# ScenOchSinneSensor.net
KiCad netlist of a schematic drawn in EAGLE
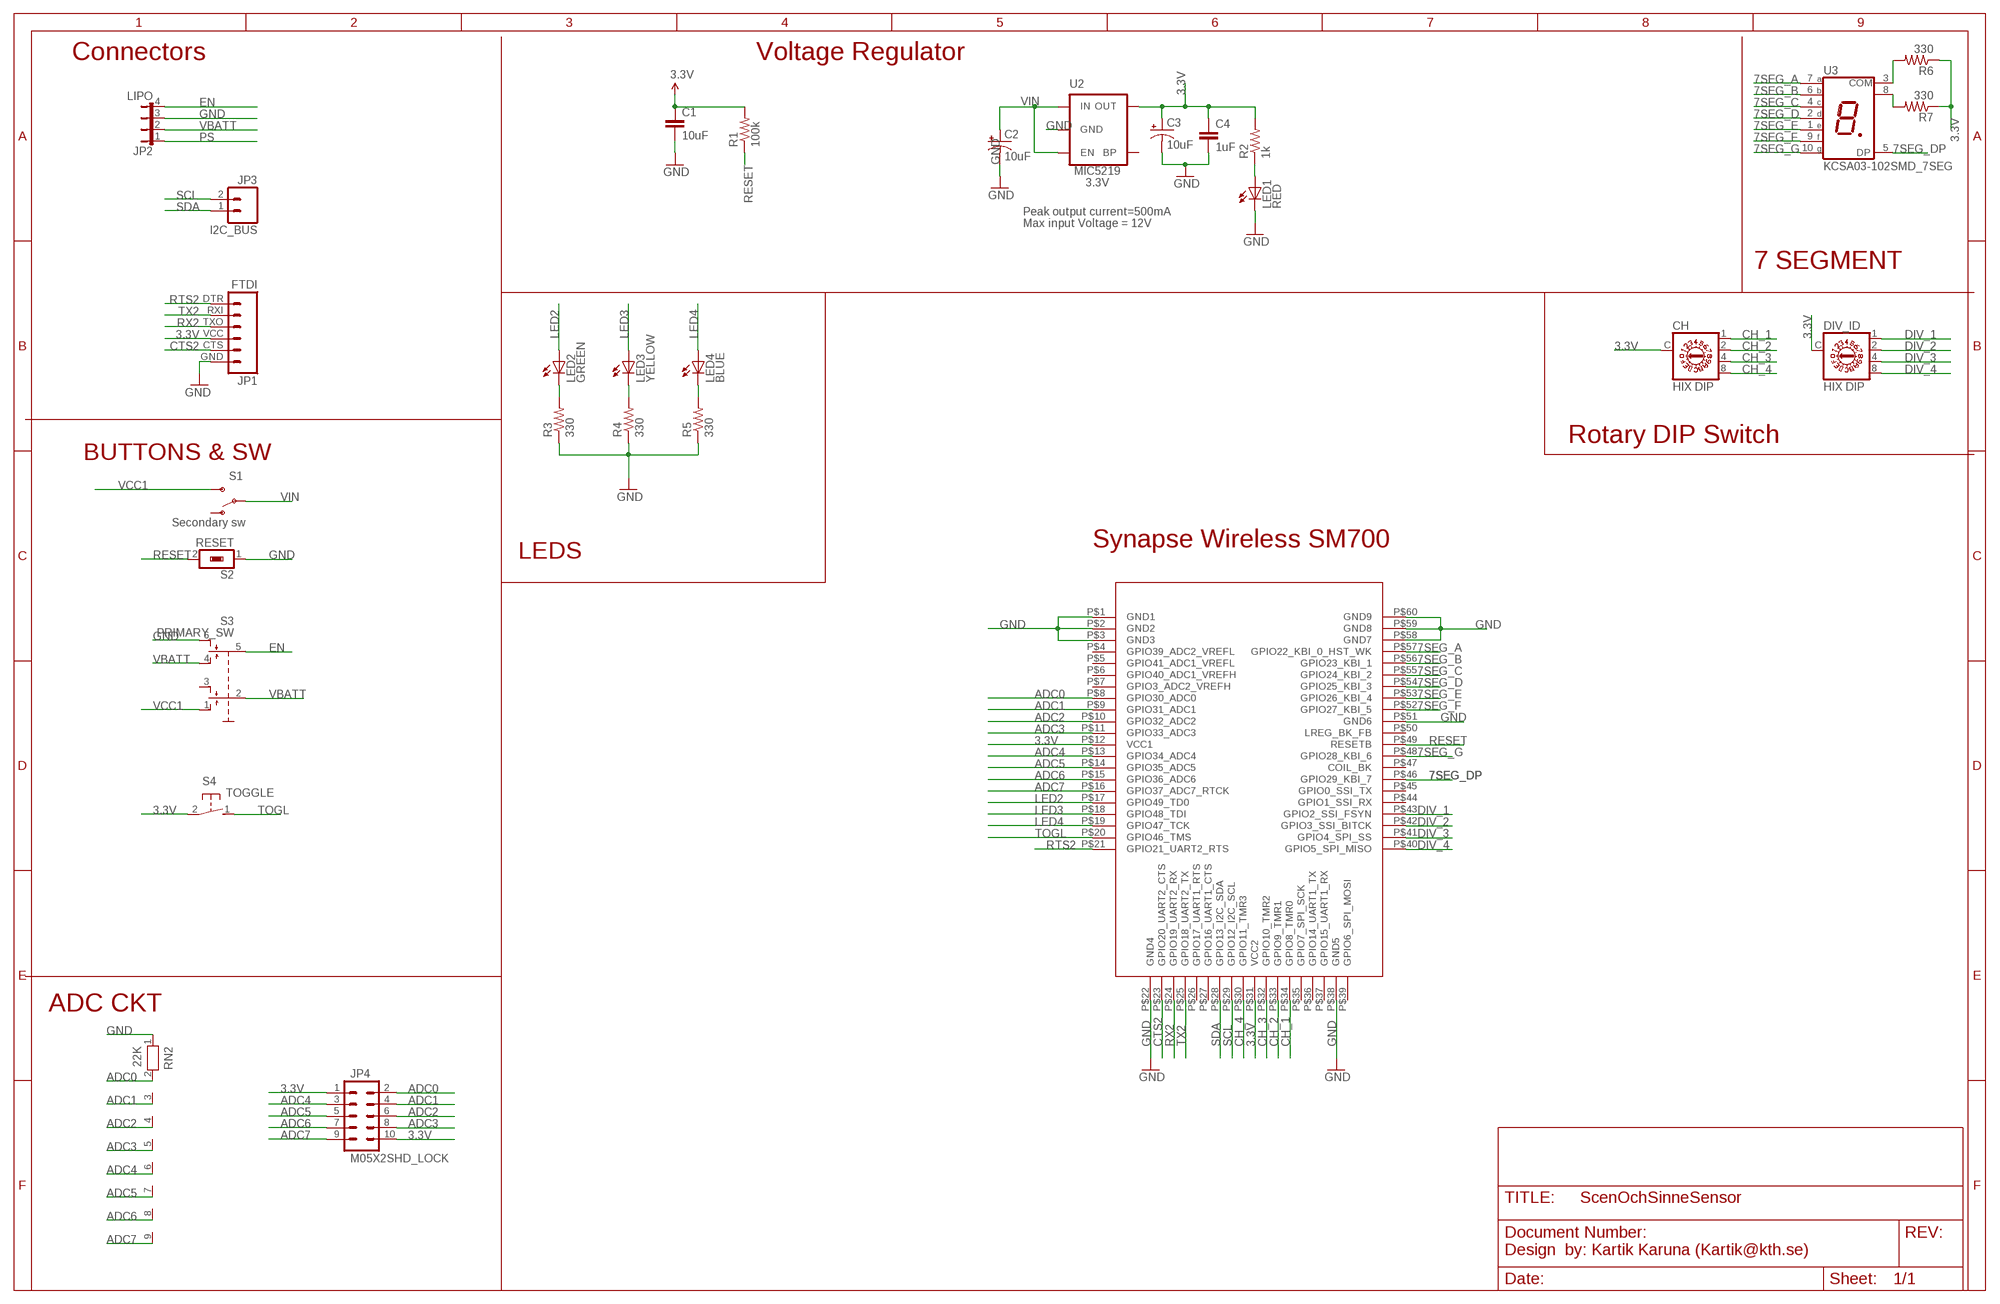
[diagram p0: schematic, sheet 1]

(export (version "E")
  (design (tool "Eeschema 10.0.6"))
  (components
    (comp (ref "C1")
      (value "10uF")
      (footprint "eagle-import:0805")
      (libsource (lib "eagle-import") (part "CAP0805"))
    )
    (comp (ref "C2")
      (value "10uF")
      (footprint "eagle-import:EIA3528")
      (libsource (lib "eagle-import") (part "CAP_POL3528"))
    )
    (comp (ref "C3")
      (value "10uF")
      (footprint "eagle-import:EIA3528")
      (libsource (lib "eagle-import") (part "CAP_POL3528"))
    )
    (comp (ref "C4")
      (value "1uF")
      (footprint "eagle-import:0805")
      (libsource (lib "eagle-import") (part "CAP0805"))
    )
    (comp (ref "CH")
      (value "HIX DIP")
      (footprint "eagle-import:A1353HEX")
      (libsource (lib "eagle-import") (part "A1353HEX"))
    )
    (comp (ref "DIV_ID")
      (value "HIX DIP")
      (footprint "eagle-import:A1353HEX")
      (libsource (lib "eagle-import") (part "A1353HEX"))
    )
    (comp (ref "JP1")
      (value "FTDI")
      (footprint "eagle-import:FTDI_BASIC")
      (libsource (lib "eagle-import") (part "FTDI_BASICPTH"))
    )
    (comp (ref "JP2")
      (value "LIPO")
      (footprint "eagle-import:JP4")
      (libsource (lib "eagle-import") (part "JP4E"))
    )
    (comp (ref "JP3")
      (value "I2C_BUS")
      (footprint "eagle-import:1X02_NO_SILK")
      (libsource (lib "eagle-import") (part "M021X02_NO_SILK"))
    )
    (comp (ref "JP4")
      (value "M05X2SHD_LOCK")
      (footprint "eagle-import:2X5-SHROUDED_LOCK")
      (libsource (lib "eagle-import") (part "M05X2SHD_LOCK"))
    )
    (comp (ref "LED1")
      (value "RED")
      (footprint "eagle-import:LED-0603")
      (libsource (lib "eagle-import") (part "LED0603"))
    )
    (comp (ref "LED2")
      (value "GREEN")
      (footprint "eagle-import:LED-0603")
      (libsource (lib "eagle-import") (part "LED0603"))
    )
    (comp (ref "LED3")
      (value "YELLOW")
      (footprint "eagle-import:LED-0603")
      (libsource (lib "eagle-import") (part "LED0603"))
    )
    (comp (ref "LED4")
      (value "BLUE")
      (footprint "eagle-import:LED-0603")
      (libsource (lib "eagle-import") (part "LED0603"))
    )
    (comp (ref "PRIMARY_SW")
      (value "S3")
      (footprint "eagle-import:SS-22")
      (libsource (lib "eagle-import") (part "SS22_SD"))
    )
    (comp (ref "R1")
      (value "100k")
      (footprint "eagle-import:0805")
      (libsource (lib "eagle-import") (part "RESISTOR0805-RES"))
    )
    (comp (ref "R2")
      (value "1k")
      (footprint "eagle-import:0805")
      (libsource (lib "eagle-import") (part "RESISTOR0805-RES"))
    )
    (comp (ref "R3")
      (value "330")
      (footprint "eagle-import:0603-RES")
      (libsource (lib "eagle-import") (part "RESISTOR0603-RES"))
    )
    (comp (ref "R4")
      (value "330")
      (footprint "eagle-import:0603-RES")
      (libsource (lib "eagle-import") (part "RESISTOR0603-RES"))
    )
    (comp (ref "R5")
      (value "330")
      (footprint "eagle-import:0603-RES")
      (libsource (lib "eagle-import") (part "RESISTOR0603-RES"))
    )
    (comp (ref "R6")
      (value "330")
      (footprint "eagle-import:0603-RES")
      (libsource (lib "eagle-import") (part "RESISTOR0603-RES"))
    )
    (comp (ref "R7")
      (value "330")
      (footprint "eagle-import:0603-RES")
      (libsource (lib "eagle-import") (part "RESISTOR0603-RES"))
    )
    (comp (ref "RN2")
      (value "22K")
      (footprint "eagle-import:RN-9")
      (libsource (lib "eagle-import") (part "RN08"))
    )
    (comp (ref "S1")
      (value "Secondary sw")
      (footprint "eagle-import:AYZ0202")
      (libsource (lib "eagle-import") (part "SWITCH-SPDTSMD"))
    )
    (comp (ref "S2")
      (value "RESET")
      (footprint "eagle-import:TYCO_FSM")
      (libsource (lib "eagle-import") (part "TYCO_FSMSFSMSM"))
    )
    (comp (ref "S4")
      (value "TOGGLE")
      (footprint "eagle-import:TYCO_FSMRACDA")
      (libsource (lib "eagle-import") (part "TYCO_FSMRACDA"))
    )
    (comp (ref "U1")
      (value "SM700PC1SMD")
      (footprint "eagle-import:SYNAPSE_SN700PC1")
      (libsource (lib "eagle-import") (part "SM700PC1SMD"))
    )
    (comp (ref "U2")
      (value "MIC5219")
      (footprint "eagle-import:SOT23-5")
      (libsource (lib "eagle-import") (part "V_REG_LDOSMD"))
    )
    (comp (ref "U3")
      (value "KCSA03-102SMD_7SEG")
      (footprint "eagle-import:SMD-7SEG")
      (libsource (lib "eagle-import") (part "KCSA03-102SMD_7SEG"))
    )
  )
  (nets
    (net (code "1") (name "/7SEG_A") (class "Default")
      (node (ref "U1") (pin "P$57") (pinfunction "GPIO22_KBI_0_HST_WK_P$57") (pintype "bidirectional"))
      (node (ref "U3") (pin "7") (pinfunction "A_7") (pintype "passive"))
    )
    (net (code "2") (name "/7SEG_B") (class "Default")
      (node (ref "U1") (pin "P$56") (pinfunction "GPIO23_KBI_1_P$56") (pintype "bidirectional"))
      (node (ref "U3") (pin "6") (pinfunction "B_6") (pintype "passive"))
    )
    (net (code "3") (name "/7SEG_C") (class "Default")
      (node (ref "U1") (pin "P$55") (pinfunction "GPIO24_KBI_2_P$55") (pintype "bidirectional"))
      (node (ref "U3") (pin "4") (pinfunction "C_4") (pintype "passive"))
    )
    (net (code "4") (name "/7SEG_D") (class "Default")
      (node (ref "U1") (pin "P$54") (pinfunction "GPIO25_KBI_3_P$54") (pintype "bidirectional"))
      (node (ref "U3") (pin "2") (pinfunction "D_2") (pintype "passive"))
    )
    (net (code "5") (name "/7SEG_DP") (class "Default")
      (node (ref "U1") (pin "P$46") (pinfunction "GPIO29_KBI_7_P$46") (pintype "bidirectional"))
      (node (ref "U3") (pin "5") (pinfunction "DP_5") (pintype "passive"))
    )
    (net (code "6") (name "/7SEG_E") (class "Default")
      (node (ref "U1") (pin "P$53") (pinfunction "GPIO26_KBI_4_P$53") (pintype "bidirectional"))
      (node (ref "U3") (pin "1") (pinfunction "E_1") (pintype "passive"))
    )
    (net (code "7") (name "/7SEG_F") (class "Default")
      (node (ref "U1") (pin "P$52") (pinfunction "GPIO27_KBI_5_P$52") (pintype "bidirectional"))
      (node (ref "U3") (pin "9") (pinfunction "F_9") (pintype "passive"))
    )
    (net (code "8") (name "/7SEG_G") (class "Default")
      (node (ref "U1") (pin "P$48") (pinfunction "GPIO28_KBI_6_P$48") (pintype "bidirectional"))
      (node (ref "U3") (pin "10") (pinfunction "G_10") (pintype "passive"))
    )
    (net (code "9") (name "/ADC0") (class "Default")
      (node (ref "JP4") (pin "2") (pinfunction "2_2") (pintype "passive"))
      (node (ref "RN2") (pin "2") (pinfunction "2_2") (pintype "passive"))
      (node (ref "U1") (pin "P$8") (pinfunction "GPIO30_ADC0_P$8") (pintype "bidirectional"))
    )
    (net (code "10") (name "/ADC1") (class "Default")
      (node (ref "JP4") (pin "4") (pinfunction "4_4") (pintype "passive"))
      (node (ref "RN2") (pin "3") (pinfunction "3_3") (pintype "passive"))
      (node (ref "U1") (pin "P$9") (pinfunction "GPIO31_ADC1_P$9") (pintype "bidirectional"))
    )
    (net (code "11") (name "/ADC2") (class "Default")
      (node (ref "JP4") (pin "6") (pinfunction "6_6") (pintype "passive"))
      (node (ref "RN2") (pin "4") (pinfunction "4_4") (pintype "passive"))
      (node (ref "U1") (pin "P$10") (pinfunction "GPIO32_ADC2_P$10") (pintype "bidirectional"))
    )
    (net (code "12") (name "/ADC3") (class "Default")
      (node (ref "JP4") (pin "8") (pinfunction "8_8") (pintype "passive"))
      (node (ref "RN2") (pin "5") (pinfunction "5_5") (pintype "passive"))
      (node (ref "U1") (pin "P$11") (pinfunction "GPIO33_ADC3_P$11") (pintype "bidirectional"))
    )
    (net (code "13") (name "/ADC4") (class "Default")
      (node (ref "JP4") (pin "3") (pinfunction "3_3") (pintype "passive"))
      (node (ref "RN2") (pin "6") (pinfunction "6_6") (pintype "passive"))
      (node (ref "U1") (pin "P$13") (pinfunction "GPIO34_ADC4_P$13") (pintype "bidirectional"))
    )
    (net (code "14") (name "/ADC5") (class "Default")
      (node (ref "JP4") (pin "5") (pinfunction "5_5") (pintype "passive"))
      (node (ref "RN2") (pin "7") (pinfunction "7_7") (pintype "passive"))
      (node (ref "U1") (pin "P$14") (pinfunction "GPIO35_ADC5_P$14") (pintype "bidirectional"))
    )
    (net (code "15") (name "/ADC6") (class "Default")
      (node (ref "JP4") (pin "7") (pinfunction "7_7") (pintype "passive"))
      (node (ref "RN2") (pin "8") (pinfunction "8_8") (pintype "passive"))
      (node (ref "U1") (pin "P$15") (pinfunction "GPIO36_ADC6_P$15") (pintype "bidirectional"))
    )
    (net (code "16") (name "/ADC7") (class "Default")
      (node (ref "JP4") (pin "9") (pinfunction "9_9") (pintype "passive"))
      (node (ref "RN2") (pin "9") (pinfunction "9_9") (pintype "passive"))
      (node (ref "U1") (pin "P$16") (pinfunction "GPIO37_ADC7_RTCK_P$16") (pintype "bidirectional"))
    )
    (net (code "17") (name "/CH_1") (class "Default")
      (node (ref "CH") (pin "1") (pinfunction "1_1") (pintype "passive"))
      (node (ref "U1") (pin "P$34") (pinfunction "GPIO8_TMR0_P$34") (pintype "bidirectional"))
    )
    (net (code "18") (name "/CH_2") (class "Default")
      (node (ref "CH") (pin "2") (pinfunction "2_2") (pintype "passive"))
      (node (ref "U1") (pin "P$33") (pinfunction "GPIO9_TMR1_P$33") (pintype "bidirectional"))
    )
    (net (code "19") (name "/CH_3") (class "Default")
      (node (ref "CH") (pin "4") (pinfunction "4_4") (pintype "passive"))
      (node (ref "U1") (pin "P$32") (pinfunction "GPIO10_TMR2_P$32") (pintype "bidirectional"))
    )
    (net (code "20") (name "/CH_4") (class "Default")
      (node (ref "CH") (pin "8") (pinfunction "8_8") (pintype "passive"))
      (node (ref "U1") (pin "P$30") (pinfunction "GPIO11_TMR3_P$30") (pintype "bidirectional"))
    )
    (net (code "21") (name "/CTS2") (class "Default")
      (node (ref "JP1") (pin "CTS") (pinfunction "5_CTS") (pintype "passive"))
      (node (ref "U1") (pin "P$23") (pinfunction "GPIO20_UART2_CTS_P$23") (pintype "bidirectional"))
    )
    (net (code "22") (name "/DIV_1") (class "Default")
      (node (ref "DIV_ID") (pin "1") (pinfunction "1_1") (pintype "passive"))
      (node (ref "U1") (pin "P$43") (pinfunction "GPIO2_SSI_FSYN_P$43") (pintype "bidirectional"))
    )
    (net (code "23") (name "/DIV_2") (class "Default")
      (node (ref "DIV_ID") (pin "2") (pinfunction "2_2") (pintype "passive"))
      (node (ref "U1") (pin "P$42") (pinfunction "GPIO3_SSI_BITCK_P$42") (pintype "bidirectional"))
    )
    (net (code "24") (name "/DIV_3") (class "Default")
      (node (ref "DIV_ID") (pin "4") (pinfunction "4_4") (pintype "passive"))
      (node (ref "U1") (pin "P$41") (pinfunction "GPIO4_SPI_SS_P$41") (pintype "bidirectional"))
    )
    (net (code "25") (name "/DIV_4") (class "Default")
      (node (ref "DIV_ID") (pin "8") (pinfunction "8_8") (pintype "passive"))
      (node (ref "U1") (pin "P$40") (pinfunction "GPIO5_SPI_MISO_P$40") (pintype "bidirectional"))
    )
    (net (code "26") (name "/EN") (class "Default")
      (node (ref "JP2") (pin "4") (pinfunction "4_4") (pintype "passive"))
      (node (ref "PRIMARY_SW") (pin "5") (pinfunction "5_5") (pintype "passive"))
    )
    (net (code "27") (name "/LED2") (class "Default")
      (node (ref "LED2") (pin "A") (pinfunction "A_A") (pintype "passive"))
      (node (ref "U1") (pin "P$17") (pinfunction "GPIO49_TD0_P$17") (pintype "bidirectional"))
    )
    (net (code "28") (name "/LED3") (class "Default")
      (node (ref "LED3") (pin "A") (pinfunction "A_A") (pintype "passive"))
      (node (ref "U1") (pin "P$18") (pinfunction "GPIO48_TDI_P$18") (pintype "bidirectional"))
    )
    (net (code "29") (name "/LED4") (class "Default")
      (node (ref "LED4") (pin "A") (pinfunction "A_A") (pintype "passive"))
      (node (ref "U1") (pin "P$19") (pinfunction "GPIO47_TCK_P$19") (pintype "bidirectional"))
    )
    (net (code "30") (name "/PS") (class "Default")
      (node (ref "JP2") (pin "1") (pinfunction "1_1") (pintype "passive"))
    )
    (net (code "31") (name "/RESET") (class "Default")
      (node (ref "R1") (pin "1") (pinfunction "1_1") (pintype "passive"))
      (node (ref "S2") (pin "2") (pinfunction "2_2") (pintype "passive"))
      (node (ref "U1") (pin "P$49") (pinfunction "RESETB_P$49") (pintype "bidirectional"))
    )
    (net (code "32") (name "/RTS2") (class "Default")
      (node (ref "JP1") (pin "DTR") (pinfunction "1_DTR") (pintype "passive"))
      (node (ref "U1") (pin "P$21") (pinfunction "GPIO21_UART2_RTS_P$21") (pintype "bidirectional"))
    )
    (net (code "33") (name "/RX2") (class "Default")
      (node (ref "JP1") (pin "TXO") (pinfunction "3_TXO") (pintype "passive"))
      (node (ref "U1") (pin "P$24") (pinfunction "GPIO19_UART2_RX_P$24") (pintype "bidirectional"))
    )
    (net (code "34") (name "/SCL") (class "Default")
      (node (ref "JP3") (pin "2") (pinfunction "2_2") (pintype "passive"))
      (node (ref "U1") (pin "P$29") (pinfunction "GPIO12_I2C_SCL_P$29") (pintype "bidirectional"))
    )
    (net (code "35") (name "/SDA") (class "Default")
      (node (ref "JP3") (pin "1") (pinfunction "1_1") (pintype "passive"))
      (node (ref "U1") (pin "P$28") (pinfunction "GPIO13_I2C_SDA_P$28") (pintype "bidirectional"))
    )
    (net (code "36") (name "/TOGL") (class "Default")
      (node (ref "S4") (pin "1") (pinfunction "1_1") (pintype "passive"))
      (node (ref "U1") (pin "P$20") (pinfunction "GPIO46_TMS_P$20") (pintype "bidirectional"))
    )
    (net (code "37") (name "/TX2") (class "Default")
      (node (ref "JP1") (pin "RXI") (pinfunction "2_RXI") (pintype "passive"))
      (node (ref "U1") (pin "P$25") (pinfunction "GPIO18_UART2_TX_P$25") (pintype "bidirectional"))
    )
    (net (code "38") (name "/VBATT") (class "Default")
      (node (ref "JP2") (pin "2") (pinfunction "2_2") (pintype "passive"))
      (node (ref "PRIMARY_SW") (pin "2") (pinfunction "2_2") (pintype "passive"))
      (node (ref "PRIMARY_SW") (pin "4") (pinfunction "4_4") (pintype "passive"))
    )
    (net (code "39") (name "/VCC1") (class "Default")
      (node (ref "PRIMARY_SW") (pin "1") (pinfunction "1_1") (pintype "passive"))
      (node (ref "S1") (pin "3") (pinfunction "S_3") (pintype "passive"))
    )
    (net (code "40") (name "/VIN") (class "Default")
      (node (ref "C2") (pin "A") (pinfunction "+_A") (pintype "passive"))
      (node (ref "S1") (pin "2") (pinfunction "P_2") (pintype "passive"))
      (node (ref "U2") (pin "1") (pinfunction "IN_1") (pintype "input"))
      (node (ref "U2") (pin "3") (pinfunction "EN_3") (pintype "input"))
    )
    (net (code "41") (name "3.3V") (class "Default")
      (node (ref "C1") (pin "1") (pinfunction "1_1") (pintype "passive"))
      (node (ref "C3") (pin "A") (pinfunction "+_A") (pintype "passive"))
      (node (ref "C4") (pin "1") (pinfunction "1_1") (pintype "passive"))
      (node (ref "CH") (pin "C") (pinfunction "C_C") (pintype "passive"))
      (node (ref "DIV_ID") (pin "C") (pinfunction "C_C") (pintype "passive"))
      (node (ref "JP1") (pin "VCC") (pinfunction "4_VCC") (pintype "passive"))
      (node (ref "JP4") (pin "1") (pinfunction "1_1") (pintype "passive"))
      (node (ref "JP4") (pin "10") (pinfunction "10_10") (pintype "passive"))
      (node (ref "R1") (pin "2") (pinfunction "2_2") (pintype "passive"))
      (node (ref "R2") (pin "2") (pinfunction "2_2") (pintype "passive"))
      (node (ref "R6") (pin "1") (pinfunction "1_1") (pintype "passive"))
      (node (ref "R7") (pin "1") (pinfunction "1_1") (pintype "passive"))
      (node (ref "S4") (pin "2") (pinfunction "2_2") (pintype "passive"))
      (node (ref "U1") (pin "P$12") (pinfunction "VCC1_P$12") (pintype "bidirectional"))
      (node (ref "U1") (pin "P$31") (pinfunction "VCC2_P$31") (pintype "bidirectional"))
      (node (ref "U2") (pin "5") (pinfunction "OUT_5") (pintype "passive"))
    )
    (net (code "42") (name "GND") (class "Default")
      (node (ref "C1") (pin "2") (pinfunction "2_2") (pintype "passive"))
      (node (ref "C2") (pin "C") (pinfunction "-_C") (pintype "passive"))
      (node (ref "C3") (pin "C") (pinfunction "-_C") (pintype "passive"))
      (node (ref "C4") (pin "2") (pinfunction "2_2") (pintype "passive"))
      (node (ref "JP1") (pin "GND") (pinfunction "6_GND") (pintype "passive"))
      (node (ref "JP2") (pin "3") (pinfunction "3_3") (pintype "passive"))
      (node (ref "LED1") (pin "C") (pinfunction "C_C") (pintype "passive"))
      (node (ref "PRIMARY_SW") (pin "6") (pinfunction "6_6") (pintype "passive"))
      (node (ref "R3") (pin "1") (pinfunction "1_1") (pintype "passive"))
      (node (ref "R4") (pin "1") (pinfunction "1_1") (pintype "passive"))
      (node (ref "R5") (pin "1") (pinfunction "1_1") (pintype "passive"))
      (node (ref "RN2") (pin "1") (pinfunction "1_1") (pintype "passive"))
      (node (ref "S2") (pin "1") (pinfunction "1_1") (pintype "passive"))
      (node (ref "U1") (pin "P$1") (pinfunction "GND1_P$1") (pintype "bidirectional"))
      (node (ref "U1") (pin "P$2") (pinfunction "GND2_P$2") (pintype "bidirectional"))
      (node (ref "U1") (pin "P$22") (pinfunction "GND4_P$22") (pintype "bidirectional"))
      (node (ref "U1") (pin "P$3") (pinfunction "GND3_P$3") (pintype "bidirectional"))
      (node (ref "U1") (pin "P$38") (pinfunction "GND5_P$38") (pintype "bidirectional"))
      (node (ref "U1") (pin "P$51") (pinfunction "GND6_P$51") (pintype "bidirectional"))
      (node (ref "U1") (pin "P$58") (pinfunction "GND7_P$58") (pintype "bidirectional"))
      (node (ref "U1") (pin "P$59") (pinfunction "GND8_P$59") (pintype "bidirectional"))
      (node (ref "U1") (pin "P$60") (pinfunction "GND9_P$60") (pintype "bidirectional"))
      (node (ref "U2") (pin "2") (pinfunction "GND_2") (pintype "input"))
    )
    (net (code "43") (name "Net-(LED1-PadA)") (class "Default")
      (node (ref "LED1") (pin "A") (pinfunction "A_A") (pintype "passive"))
      (node (ref "R2") (pin "1") (pinfunction "1_1") (pintype "passive"))
    )
    (net (code "44") (name "Net-(LED2-PadC)") (class "Default")
      (node (ref "LED2") (pin "C") (pinfunction "C_C") (pintype "passive"))
      (node (ref "R3") (pin "2") (pinfunction "2_2") (pintype "passive"))
    )
    (net (code "45") (name "Net-(LED3-PadC)") (class "Default")
      (node (ref "LED3") (pin "C") (pinfunction "C_C") (pintype "passive"))
      (node (ref "R4") (pin "2") (pinfunction "2_2") (pintype "passive"))
    )
    (net (code "46") (name "Net-(LED4-PadC)") (class "Default")
      (node (ref "LED4") (pin "C") (pinfunction "C_C") (pintype "passive"))
      (node (ref "R5") (pin "2") (pinfunction "2_2") (pintype "passive"))
    )
    (net (code "47") (name "Net-(R6-Pad2)") (class "Default")
      (node (ref "R6") (pin "2") (pinfunction "2_2") (pintype "passive"))
      (node (ref "U3") (pin "3") (pinfunction "COM_3") (pintype "passive"))
    )
    (net (code "48") (name "Net-(R7-Pad2)") (class "Default")
      (node (ref "R7") (pin "2") (pinfunction "2_2") (pintype "passive"))
      (node (ref "U3") (pin "8") (pinfunction "COM_8") (pintype "passive"))
    )
    (net (code "49") (name "unconnected-(PRIMARY_SW-Pad3)") (class "Default")
      (node (ref "PRIMARY_SW") (pin "3") (pinfunction "3_3") (pintype "passive"))
    )
    (net (code "50") (name "unconnected-(S1-O-Pad1)") (class "Default")
      (node (ref "S1") (pin "1") (pinfunction "O_1") (pintype "passive"))
    )
    (net (code "51") (name "unconnected-(U1-COIL_BK-PadP$47)") (class "Default")
      (node (ref "U1") (pin "P$47") (pinfunction "COIL_BK_P$47") (pintype "bidirectional"))
    )
    (net (code "52") (name "unconnected-(U1-GPIO0_SSI_TX-PadP$45)") (class "Default")
      (node (ref "U1") (pin "P$45") (pinfunction "GPIO0_SSI_TX_P$45") (pintype "bidirectional"))
    )
    (net (code "53") (name "unconnected-(U1-GPIO1_SSI_RX-PadP$44)") (class "Default")
      (node (ref "U1") (pin "P$44") (pinfunction "GPIO1_SSI_RX_P$44") (pintype "bidirectional"))
    )
    (net (code "54") (name "unconnected-(U1-GPIO3_ADC2_VREFH-PadP$7)") (class "Default")
      (node (ref "U1") (pin "P$7") (pinfunction "GPIO3_ADC2_VREFH_P$7") (pintype "bidirectional"))
    )
    (net (code "55") (name "unconnected-(U1-GPIO6_SPI_MOSI-PadP$39)") (class "Default")
      (node (ref "U1") (pin "P$39") (pinfunction "GPIO6_SPI_MOSI_P$39") (pintype "bidirectional"))
    )
    (net (code "56") (name "unconnected-(U1-GPIO7_SPI_SCK-PadP$35)") (class "Default")
      (node (ref "U1") (pin "P$35") (pinfunction "GPIO7_SPI_SCK_P$35") (pintype "bidirectional"))
    )
    (net (code "57") (name "unconnected-(U1-GPIO14_UART1_TX-PadP$36)") (class "Default")
      (node (ref "U1") (pin "P$36") (pinfunction "GPIO14_UART1_TX_P$36") (pintype "bidirectional"))
    )
    (net (code "58") (name "unconnected-(U1-GPIO15_UART1_RX-PadP$37)") (class "Default")
      (node (ref "U1") (pin "P$37") (pinfunction "GPIO15_UART1_RX_P$37") (pintype "bidirectional"))
    )
    (net (code "59") (name "unconnected-(U1-GPIO16_UART1_CTS-PadP$27)") (class "Default")
      (node (ref "U1") (pin "P$27") (pinfunction "GPIO16_UART1_CTS_P$27") (pintype "bidirectional"))
    )
    (net (code "60") (name "unconnected-(U1-GPIO17_UART1_RTS-PadP$26)") (class "Default")
      (node (ref "U1") (pin "P$26") (pinfunction "GPIO17_UART1_RTS_P$26") (pintype "bidirectional"))
    )
    (net (code "61") (name "unconnected-(U1-GPIO39_ADC2_VREFL-PadP$4)") (class "Default")
      (node (ref "U1") (pin "P$4") (pinfunction "GPIO39_ADC2_VREFL_P$4") (pintype "bidirectional"))
    )
    (net (code "62") (name "unconnected-(U1-GPIO40_ADC1_VREFH-PadP$6)") (class "Default")
      (node (ref "U1") (pin "P$6") (pinfunction "GPIO40_ADC1_VREFH_P$6") (pintype "bidirectional"))
    )
    (net (code "63") (name "unconnected-(U1-GPIO41_ADC1_VREFL-PadP$5)") (class "Default")
      (node (ref "U1") (pin "P$5") (pinfunction "GPIO41_ADC1_VREFL_P$5") (pintype "bidirectional"))
    )
    (net (code "64") (name "unconnected-(U1-LREG_BK_FB-PadP$50)") (class "Default")
      (node (ref "U1") (pin "P$50") (pinfunction "LREG_BK_FB_P$50") (pintype "bidirectional"))
    )
    (net (code "65") (name "unconnected-(U2-BP-Pad4)") (class "Default")
      (node (ref "U2") (pin "4") (pinfunction "BP_4") (pintype "input"))
    )
  )
)
